# ADC.net
KiCad netlist of a schematic drawn in Altium Designer
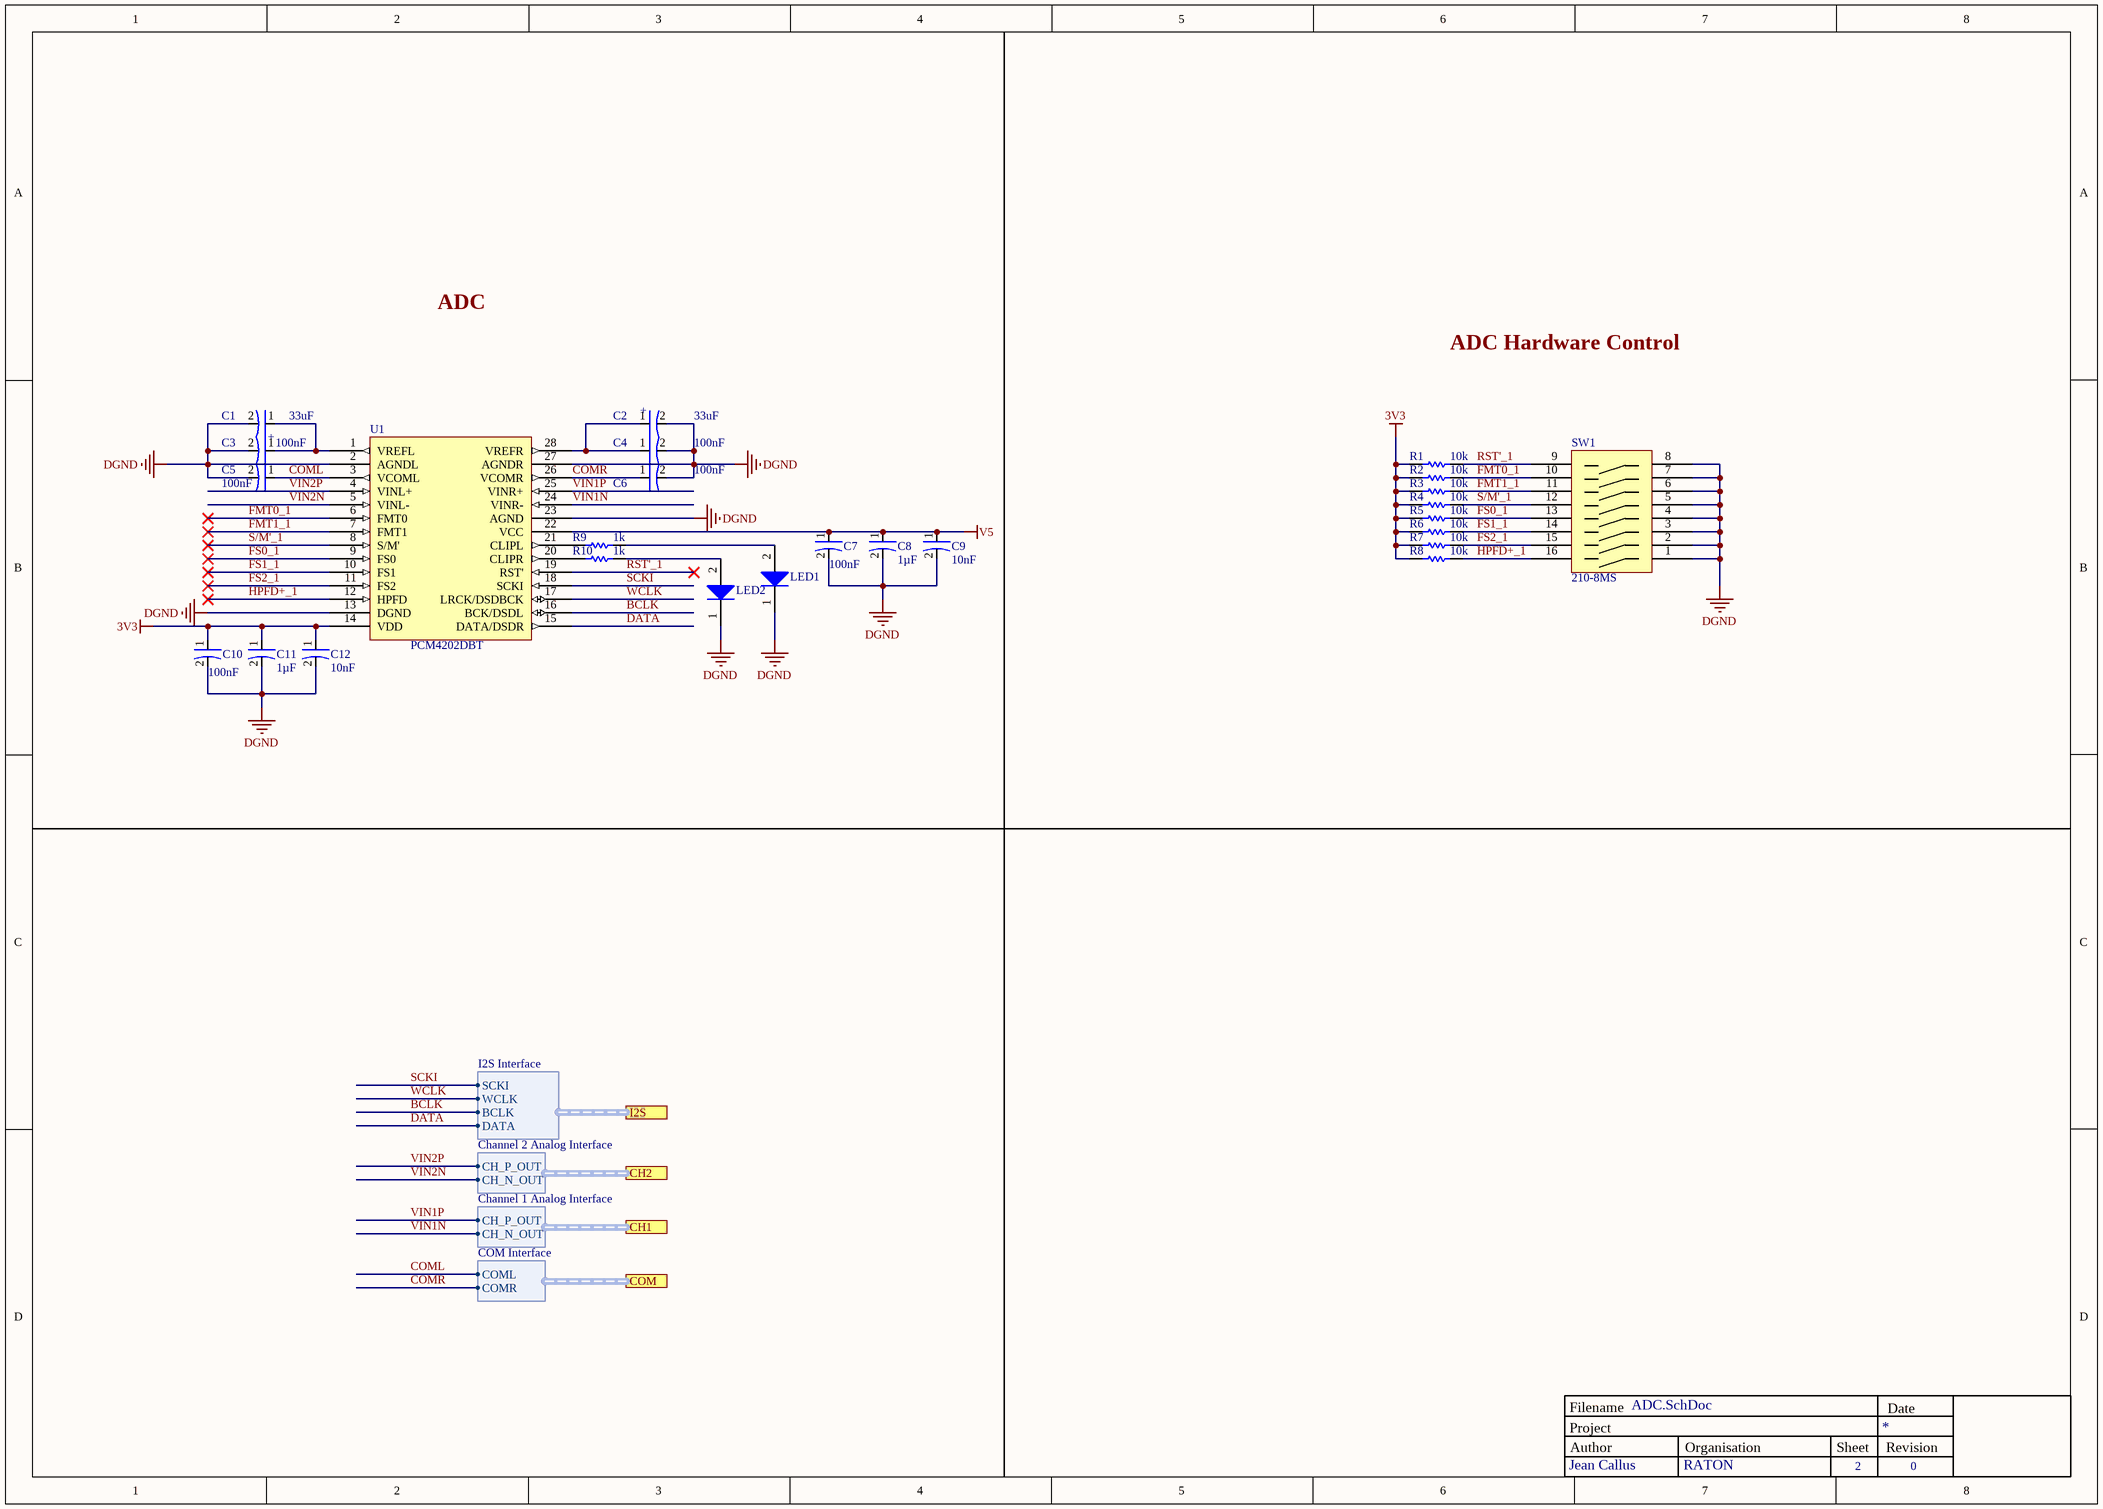
[diagram p0: ADC.SchDoc]

(export (version "E")
  (design (tool "Eeschema 10.0.6"))
  (components
    (comp (ref "C1")
      (value "33uF")
      (footprint "CAPMP6032X26N")
      (description "CAP-33uF-TANT-C")
      (fields (field (name "MANUFACTURER") "AVX") (field (name "Comment") "CAP 33uF TANT C"))
      (libsource (lib "") (part "Symbol_3"))
    )
    (comp (ref "C2")
      (value "33uF")
      (footprint "CAPMP6032X26N")
      (description "CAP-33uF-TANT-C")
      (fields (field (name "MANUFACTURER") "AVX") (field (name "Comment") "CAP 33uF TANT C"))
      (libsource (lib "") (part "Symbol_3"))
    )
    (comp (ref "C3")
      (value "100nF")
      (footprint "0805-M")
      (description "CAP-0.1uF-CER-0805-50V- X7R-5%")
      (fields
        (field (name "MANUFACTURER") "Generic")
        (field (name "Comment") "CAP 0.1uF CER 0805 50V  X7R 5%")
      )
      (libsource (lib "") (part "Symbol_1"))
    )
    (comp (ref "C4")
      (value "100nF")
      (footprint "0805-M")
      (description "CAP-0.1uF-CER-0805-50V- X7R-5%")
      (fields
        (field (name "MANUFACTURER") "Generic")
        (field (name "Comment") "CAP 0.1uF CER 0805 50V  X7R 5%")
      )
      (libsource (lib "") (part "Symbol_1"))
    )
    (comp (ref "C5")
      (value "100nF")
      (footprint "0805-M")
      (description "CAP-0.1uF-CER-0805-50V- X7R-5%")
      (fields
        (field (name "MANUFACTURER") "Generic")
        (field (name "Comment") "CAP 0.1uF CER 0805 50V  X7R 5%")
      )
      (libsource (lib "") (part "Symbol_1"))
    )
    (comp (ref "C6")
      (value "100nF")
      (footprint "0805-M")
      (description "CAP-0.1uF-CER-0805-50V- X7R-5%")
      (fields
        (field (name "MANUFACTURER") "Generic")
        (field (name "Comment") "CAP 0.1uF CER 0805 50V  X7R 5%")
      )
      (libsource (lib "") (part "Symbol_1"))
    )
    (comp (ref "C7")
      (value "100nF")
      (footprint "0805-M")
      (description "CAP-0.1uF-CER-0805-50V- X7R-5%")
      (fields
        (field (name "MANUFACTURER") "Generic")
        (field (name "Comment") "CAP 0.1uF CER 0805 50V  X7R 5%")
      )
      (libsource (lib "") (part "Symbol_1"))
    )
    (comp (ref "C8")
      (value "1µF")
      (footprint "0805-L")
      (description "CAP-1uF-CER-0805-50V-X7R-10%")
      (fields (field (name "MANUFACTURER") "Generic") (field (name "Comment") "CAP 1uF CER 0805 50V X7R 10%"))
      (libsource (lib "") (part "Symbol_1"))
    )
    (comp (ref "C9")
      (value "10nF")
      (footprint "0805-M")
      (description "CAP-10nF-CER-0805-50V-X7R-10%")
      (fields
        (field (name "MANUFACTURER") "Generic")
        (field (name "Comment") "CAP 10nF CER 0805 50V X7R 10%")
      )
      (libsource (lib "") (part "Symbol_1"))
    )
    (comp (ref "C10")
      (value "100nF")
      (footprint "0805-M")
      (description "CAP-0.1uF-CER-0805-50V- X7R-5%")
      (fields
        (field (name "MANUFACTURER") "Generic")
        (field (name "Comment") "CAP 0.1uF CER 0805 50V  X7R 5%")
      )
      (libsource (lib "") (part "Symbol_1"))
    )
    (comp (ref "C11")
      (value "1µF")
      (footprint "0805-L")
      (description "CAP-1uF-CER-0805-50V-X7R-10%")
      (fields (field (name "MANUFACTURER") "Generic") (field (name "Comment") "CAP 1uF CER 0805 50V X7R 10%"))
      (libsource (lib "") (part "Symbol_1"))
    )
    (comp (ref "C12")
      (value "10nF")
      (footprint "0805-M")
      (description "CAP-10nF-CER-0805-50V-X7R-10%")
      (fields
        (field (name "MANUFACTURER") "Generic")
        (field (name "Comment") "CAP 10nF CER 0805 50V X7R 10%")
      )
      (libsource (lib "") (part "Symbol_1"))
    )
    (comp (ref "LED1")
      (value "LED 0603 Red 20mA 1.7V")
      (footprint "0603 Generic")
      (description "LED-0603-Red-20mA-1.7V-STOCK")
      (fields (field (name "MANUFACTURER") "Generic"))
      (libsource (lib "") (part "Symbol_2"))
    )
    (comp (ref "LED2")
      (value "LED 0603 Red 20mA 1.7V")
      (footprint "0603 Generic")
      (description "LED-0603-Red-20mA-1.7V-STOCK")
      (fields (field (name "MANUFACTURER") "Generic"))
      (libsource (lib "") (part "Symbol_2"))
    )
    (comp (ref "R1")
      (value "10k")
      (footprint "0805-M")
      (description "RES-10k-0805-125mW-1%")
      (fields (field (name "MANUFACTURER") "Generic") (field (name "Comment") "RES 10k 0805 125mW 1%"))
      (libsource (lib "University of Malta - MEMENTO") (part "Symbol"))
    )
    (comp (ref "R2")
      (value "10k")
      (footprint "0805-M")
      (description "RES-10k-0805-125mW-1%")
      (fields (field (name "MANUFACTURER") "Generic") (field (name "Comment") "RES 10k 0805 125mW 1%"))
      (libsource (lib "University of Malta - MEMENTO") (part "Symbol"))
    )
    (comp (ref "R3")
      (value "10k")
      (footprint "0805-M")
      (description "RES-10k-0805-125mW-1%")
      (fields (field (name "MANUFACTURER") "Generic") (field (name "Comment") "RES 10k 0805 125mW 1%"))
      (libsource (lib "University of Malta - MEMENTO") (part "Symbol"))
    )
    (comp (ref "R4")
      (value "10k")
      (footprint "0805-M")
      (description "RES-10k-0805-125mW-1%")
      (fields (field (name "MANUFACTURER") "Generic") (field (name "Comment") "RES 10k 0805 125mW 1%"))
      (libsource (lib "University of Malta - MEMENTO") (part "Symbol"))
    )
    (comp (ref "R5")
      (value "10k")
      (footprint "0805-M")
      (description "RES-10k-0805-125mW-1%")
      (fields (field (name "MANUFACTURER") "Generic") (field (name "Comment") "RES 10k 0805 125mW 1%"))
      (libsource (lib "University of Malta - MEMENTO") (part "Symbol"))
    )
    (comp (ref "R6")
      (value "10k")
      (footprint "0805-M")
      (description "RES-10k-0805-125mW-1%")
      (fields (field (name "MANUFACTURER") "Generic") (field (name "Comment") "RES 10k 0805 125mW 1%"))
      (libsource (lib "University of Malta - MEMENTO") (part "Symbol"))
    )
    (comp (ref "R7")
      (value "10k")
      (footprint "0805-M")
      (description "RES-10k-0805-125mW-1%")
      (fields (field (name "MANUFACTURER") "Generic") (field (name "Comment") "RES 10k 0805 125mW 1%"))
      (libsource (lib "University of Malta - MEMENTO") (part "Symbol"))
    )
    (comp (ref "R8")
      (value "10k")
      (footprint "0805-M")
      (description "RES-10k-0805-125mW-1%")
      (fields (field (name "MANUFACTURER") "Generic") (field (name "Comment") "RES 10k 0805 125mW 1%"))
      (libsource (lib "University of Malta - MEMENTO") (part "Symbol"))
    )
    (comp (ref "R9")
      (value "1k")
      (footprint "0805-M")
      (description "RES-1k-0805-125mW-5%")
      (fields (field (name "MANUFACTURER") "Generic") (field (name "Comment") "RES 1k 0805 125mW 5%"))
      (libsource (lib "University of Malta - MEMENTO") (part "Symbol"))
    )
    (comp (ref "R10")
      (value "1k")
      (footprint "0805-M")
      (description "RES-1k-0805-125mW-5%")
      (fields (field (name "MANUFACTURER") "Generic") (field (name "Comment") "RES 1k 0805 125mW 5%"))
      (libsource (lib "University of Malta - MEMENTO") (part "Symbol"))
    )
    (comp (ref "SW1")
      (value "210-8MS")
      (footprint "210-8MS")
      (description "SWITCH DIP SMD SPST 8 100mA 50V")
      (fields (field (name "MANUFACTURER") "C&K Components") (field (name "DESIGN ITEM ID") "210-8MS"))
      (libsource (lib "University of Malta - MEMENTO") (part "210-8MS"))
    )
    (comp (ref "U1")
      (value "PCM4202DBT")
      (footprint "SOP65P780X200-28N")
      (libsource (lib "University of Malta - MEMENTO") (part "PCM4202DBT"))
    )
  )
  (nets
    (net (code "8") (name "/BCLK") (class "Default")
      (node (ref "U1") (pin "16") (pinfunction "BCK/DSDL_16") (pintype "bidirectional"))
    )
    (net (code "9") (name "/COML") (class "Default")
      (node (ref "C5") (pin "1") (pinfunction "Anode_1") (pintype "passive"))
      (node (ref "U1") (pin "3") (pinfunction "VCOML_3") (pintype "output"))
    )
    (net (code "10") (name "/COMR") (class "Default")
      (node (ref "C6") (pin "1") (pinfunction "Anode_1") (pintype "passive"))
      (node (ref "U1") (pin "26") (pinfunction "VCOMR_26") (pintype "output"))
    )
    (net (code "11") (name "/DATA") (class "Default")
      (node (ref "U1") (pin "15") (pinfunction "DATA/DSDR_15") (pintype "output"))
    )
    (net (code "12") (name "/FMT0_1") (class "Default")
      (node (ref "R2") (pin "1") (pinfunction "1_1") (pintype "passive"))
      (node (ref "SW1") (pin "10") (pinfunction "SW3.in_10") (pintype "passive"))
      (node (ref "U1") (pin "6") (pinfunction "FMT0_6") (pintype "input"))
    )
    (net (code "13") (name "/FMT1_1") (class "Default")
      (node (ref "R3") (pin "1") (pinfunction "1_1") (pintype "passive"))
      (node (ref "SW1") (pin "11") (pinfunction "SW2.in_11") (pintype "passive"))
      (node (ref "U1") (pin "7") (pinfunction "FMT1_7") (pintype "input"))
    )
    (net (code "14") (name "/FS0_1") (class "Default")
      (node (ref "R5") (pin "1") (pinfunction "1_1") (pintype "passive"))
      (node (ref "SW1") (pin "13") (pinfunction "SW4.in_13") (pintype "passive"))
      (node (ref "U1") (pin "9") (pinfunction "FS0_9") (pintype "input"))
    )
    (net (code "15") (name "/FS1_1") (class "Default")
      (node (ref "R6") (pin "1") (pinfunction "1_1") (pintype "passive"))
      (node (ref "SW1") (pin "14") (pinfunction "SW3.in_14") (pintype "passive"))
      (node (ref "U1") (pin "10") (pinfunction "FS1_10") (pintype "input"))
    )
    (net (code "16") (name "/FS2_1") (class "Default")
      (node (ref "R7") (pin "1") (pinfunction "1_1") (pintype "passive"))
      (node (ref "SW1") (pin "15") (pinfunction "SW2.in_15") (pintype "passive"))
      (node (ref "U1") (pin "11") (pinfunction "FS2_11") (pintype "input"))
    )
    (net (code "17") (name "/HPFD+_1") (class "Default")
      (node (ref "R8") (pin "1") (pinfunction "1_1") (pintype "passive"))
      (node (ref "SW1") (pin "16") (pinfunction "SW1_16") (pintype "passive"))
      (node (ref "U1") (pin "12") (pinfunction "HPFD_12") (pintype "input"))
    )
    (net (code "18") (name "/RST'_1") (class "Default")
      (node (ref "R1") (pin "1") (pinfunction "1_1") (pintype "passive"))
      (node (ref "SW1") (pin "9") (pinfunction "SW4.in_9") (pintype "passive"))
      (node (ref "U1") (pin "19") (pinfunction "RST'_19") (pintype "input"))
    )
    (net (code "19") (name "/SCKI") (class "Default")
      (node (ref "U1") (pin "18") (pinfunction "SCKI_18") (pintype "input"))
    )
    (net (code "20") (name "/S{slash}M'_1") (class "Default")
      (node (ref "R4") (pin "1") (pinfunction "1_1") (pintype "passive"))
      (node (ref "SW1") (pin "12") (pinfunction "SW1.in_12") (pintype "passive"))
      (node (ref "U1") (pin "8") (pinfunction "S/M'_8") (pintype "input"))
    )
    (net (code "21") (name "/VIN1N") (class "Default")
      (node (ref "U1") (pin "24") (pinfunction "VINR-_24") (pintype "input"))
    )
    (net (code "22") (name "/VIN1P") (class "Default")
      (node (ref "U1") (pin "25") (pinfunction "VINR+_25") (pintype "input"))
    )
    (net (code "23") (name "/VIN2N") (class "Default")
      (node (ref "U1") (pin "5") (pinfunction "VINL-_5") (pintype "input"))
    )
    (net (code "24") (name "/VIN2P") (class "Default")
      (node (ref "U1") (pin "4") (pinfunction "VINL+_4") (pintype "input"))
    )
    (net (code "25") (name "/WCLK") (class "Default")
      (node (ref "U1") (pin "17") (pinfunction "LRCK/DSDBCK_17") (pintype "bidirectional"))
    )
    (net (code "30") (name "3V3") (class "Default")
      (node (ref "C10") (pin "1") (pinfunction "Anode_1") (pintype "passive"))
      (node (ref "C11") (pin "1") (pinfunction "Anode_1") (pintype "passive"))
      (node (ref "C12") (pin "1") (pinfunction "Anode_1") (pintype "passive"))
      (node (ref "R1") (pin "2") (pinfunction "2_2") (pintype "passive"))
      (node (ref "R2") (pin "2") (pinfunction "2_2") (pintype "passive"))
      (node (ref "R3") (pin "2") (pinfunction "2_2") (pintype "passive"))
      (node (ref "R4") (pin "2") (pinfunction "2_2") (pintype "passive"))
      (node (ref "R5") (pin "2") (pinfunction "2_2") (pintype "passive"))
      (node (ref "R6") (pin "2") (pinfunction "2_2") (pintype "passive"))
      (node (ref "R7") (pin "2") (pinfunction "2_2") (pintype "passive"))
      (node (ref "R8") (pin "2") (pinfunction "2_2") (pintype "passive"))
      (node (ref "U1") (pin "14") (pinfunction "VDD_14") (pintype "power_in"))
    )
    (net (code "31") (name "DGND") (class "Default")
      (node (ref "C1") (pin "2") (pinfunction "Cathode_2") (pintype "passive"))
      (node (ref "C10") (pin "2") (pinfunction "Cathode_2") (pintype "passive"))
      (node (ref "C11") (pin "2") (pinfunction "Cathode_2") (pintype "passive"))
      (node (ref "C12") (pin "2") (pinfunction "Cathode_2") (pintype "passive"))
      (node (ref "C2") (pin "2") (pinfunction "Cathode_2") (pintype "passive"))
      (node (ref "C3") (pin "2") (pinfunction "Cathode_2") (pintype "passive"))
      (node (ref "C4") (pin "2") (pinfunction "Cathode_2") (pintype "passive"))
      (node (ref "C5") (pin "2") (pinfunction "Cathode_2") (pintype "passive"))
      (node (ref "C6") (pin "2") (pinfunction "Cathode_2") (pintype "passive"))
      (node (ref "C7") (pin "2") (pinfunction "Cathode_2") (pintype "passive"))
      (node (ref "C8") (pin "2") (pinfunction "Cathode_2") (pintype "passive"))
      (node (ref "C9") (pin "2") (pinfunction "Cathode_2") (pintype "passive"))
      (node (ref "LED1") (pin "1") (pinfunction "1_1") (pintype "passive"))
      (node (ref "LED2") (pin "1") (pinfunction "1_1") (pintype "passive"))
      (node (ref "SW1") (pin "1") (pinfunction "SW1_1") (pintype "passive"))
      (node (ref "SW1") (pin "2") (pinfunction "SW2_2") (pintype "passive"))
      (node (ref "SW1") (pin "3") (pinfunction "SW3_3") (pintype "passive"))
      (node (ref "SW1") (pin "4") (pinfunction "SW4_4") (pintype "passive"))
      (node (ref "SW1") (pin "5") (pinfunction "SW1_5") (pintype "passive"))
      (node (ref "SW1") (pin "6") (pinfunction "SW2_6") (pintype "passive"))
      (node (ref "SW1") (pin "7") (pinfunction "7_7") (pintype "passive"))
      (node (ref "SW1") (pin "8") (pinfunction "SW4_8") (pintype "passive"))
      (node (ref "U1") (pin "13") (pinfunction "DGND_13") (pintype "power_in"))
      (node (ref "U1") (pin "2") (pinfunction "AGNDL_2") (pintype "power_in"))
      (node (ref "U1") (pin "23") (pinfunction "AGND_23") (pintype "power_in"))
      (node (ref "U1") (pin "27") (pinfunction "AGNDR_27") (pintype "power_in"))
    )
    (net (code "32") (name "Net-(C1-Anode)") (class "Default")
      (node (ref "C1") (pin "1") (pinfunction "Anode_1") (pintype "passive"))
      (node (ref "C3") (pin "1") (pinfunction "Anode_1") (pintype "passive"))
      (node (ref "U1") (pin "1") (pinfunction "VREFL_1") (pintype "output"))
    )
    (net (code "33") (name "Net-(C2-Anode)") (class "Default")
      (node (ref "C2") (pin "1") (pinfunction "Anode_1") (pintype "passive"))
      (node (ref "C4") (pin "1") (pinfunction "Anode_1") (pintype "passive"))
      (node (ref "U1") (pin "28") (pinfunction "VREFR_28") (pintype "output"))
    )
    (net (code "34") (name "Net-(LED1-Pad2)") (class "Default")
      (node (ref "LED1") (pin "2") (pinfunction "2_2") (pintype "passive"))
      (node (ref "R9") (pin "2") (pinfunction "2_2") (pintype "passive"))
    )
    (net (code "35") (name "Net-(LED2-Pad2)") (class "Default")
      (node (ref "LED2") (pin "2") (pinfunction "2_2") (pintype "passive"))
      (node (ref "R10") (pin "2") (pinfunction "2_2") (pintype "passive"))
    )
    (net (code "36") (name "Net-(U1-CLIPL)") (class "Default")
      (node (ref "R9") (pin "1") (pinfunction "1_1") (pintype "passive"))
      (node (ref "U1") (pin "21") (pinfunction "CLIPL_21") (pintype "output"))
    )
    (net (code "37") (name "Net-(U1-CLIPR)") (class "Default")
      (node (ref "R10") (pin "1") (pinfunction "1_1") (pintype "passive"))
      (node (ref "U1") (pin "20") (pinfunction "CLIPR_20") (pintype "output"))
    )
    (net (code "38") (name "V5") (class "Default")
      (node (ref "C7") (pin "1") (pinfunction "Anode_1") (pintype "passive"))
      (node (ref "C8") (pin "1") (pinfunction "Anode_1") (pintype "passive"))
      (node (ref "C9") (pin "1") (pinfunction "Anode_1") (pintype "passive"))
      (node (ref "U1") (pin "22") (pinfunction "VCC_22") (pintype "power_in"))
    )
  )
)
